# WL_RFFC.net
KiCad netlist of a schematic drawn in Altium Designer
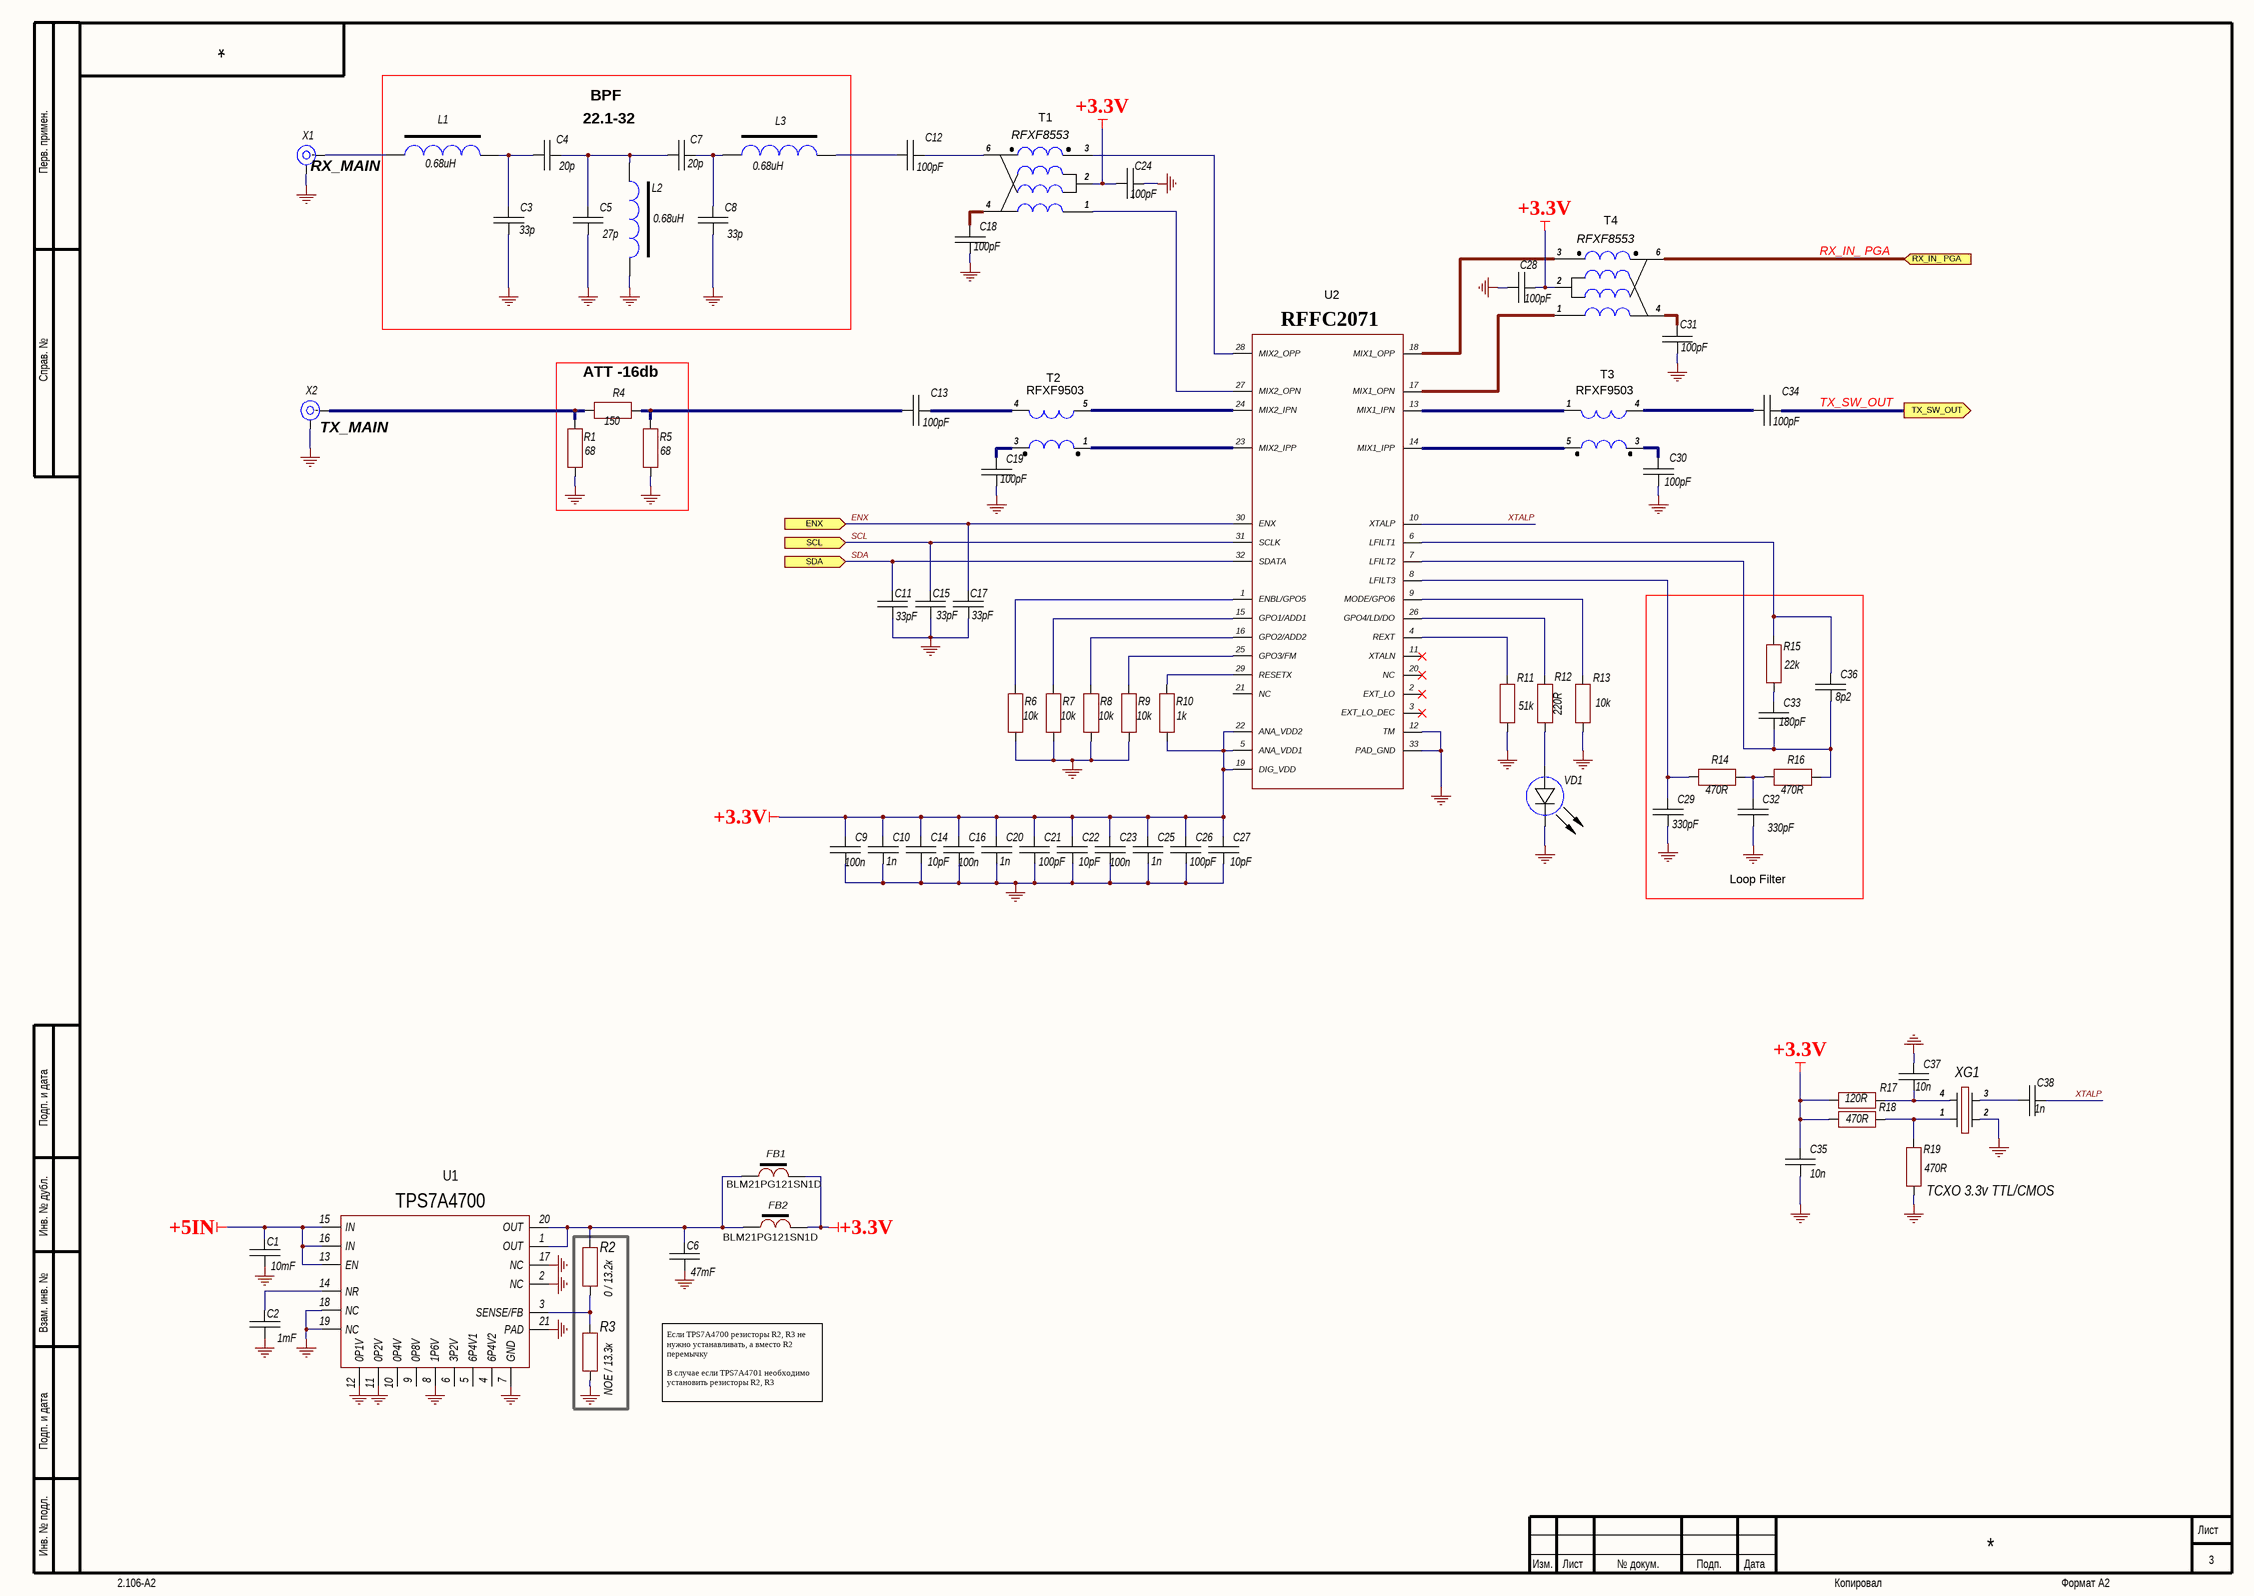
[diagram p0: WL_RFFC.SchDoc]

(export (version "E")
  (design (tool "Eeschema 10.0.6"))
  (components
    (comp (ref "C1")
      (value "10mF")
      (footprint "standard:CH1206C")
      (libsource (lib "Discrete") (part "Capacitor"))
    )
    (comp (ref "C2")
      (value "1mF")
      (footprint "standard:CH0805C")
      (libsource (lib "Discrete") (part "Capacitor"))
    )
    (comp (ref "C3")
      (value "33p")
      (footprint "standard:CH0805C")
      (libsource (lib "Discrete") (part "Capacitor"))
    )
    (comp (ref "C4")
      (value "20p")
      (footprint "standard:CH0805C")
      (libsource (lib "Discrete") (part "Capacitor"))
    )
    (comp (ref "C5")
      (value "27p")
      (footprint "standard:CH0805C")
      (libsource (lib "Discrete") (part "Capacitor"))
    )
    (comp (ref "C6")
      (value "47mF")
      (footprint "standard:CH1206C")
      (libsource (lib "Discrete") (part "Capacitor"))
    )
    (comp (ref "C7")
      (value "20p")
      (footprint "standard:CH0805C")
      (libsource (lib "Discrete") (part "Capacitor"))
    )
    (comp (ref "C8")
      (value "33p")
      (footprint "standard:CH0805C")
      (libsource (lib "Discrete") (part "Capacitor"))
    )
    (comp (ref "C9")
      (value "100n")
      (footprint "standard:CH0805C")
      (libsource (lib "Discrete") (part "Capacitor"))
    )
    (comp (ref "C10")
      (value "1n")
      (footprint "standard:CH0805C")
      (libsource (lib "Discrete") (part "Capacitor"))
    )
    (comp (ref "C11")
      (value "33pF")
      (footprint "standard:CH0805C")
      (libsource (lib "Discrete") (part "Capacitor"))
    )
    (comp (ref "C12")
      (value "100pF")
      (footprint "standard:CH0805C")
      (libsource (lib "Discrete") (part "Capacitor"))
    )
    (comp (ref "C13")
      (value "100pF")
      (footprint "standard:CH0805C")
      (libsource (lib "Discrete") (part "Capacitor"))
    )
    (comp (ref "C14")
      (value "10pF")
      (footprint "standard:CH0805C")
      (libsource (lib "Discrete") (part "Capacitor"))
    )
    (comp (ref "C15")
      (value "33pF")
      (footprint "standard:CH0805C")
      (libsource (lib "Discrete") (part "Capacitor"))
    )
    (comp (ref "C16")
      (value "100n")
      (footprint "standard:CH0805C")
      (libsource (lib "Discrete") (part "Capacitor"))
    )
    (comp (ref "C17")
      (value "33pF")
      (footprint "standard:CH0805C")
      (libsource (lib "Discrete") (part "Capacitor"))
    )
    (comp (ref "C18")
      (value "100pF")
      (footprint "standard:CH0805C")
      (libsource (lib "Discrete") (part "Capacitor"))
    )
    (comp (ref "C19")
      (value "100pF")
      (footprint "standard:CH0805C")
      (libsource (lib "Discrete") (part "Capacitor"))
    )
    (comp (ref "C20")
      (value "1n")
      (footprint "standard:CH0805C")
      (libsource (lib "Discrete") (part "Capacitor"))
    )
    (comp (ref "C21")
      (value "100pF")
      (footprint "standard:CH0805C")
      (libsource (lib "Discrete") (part "Capacitor"))
    )
    (comp (ref "C22")
      (value "10pF")
      (footprint "standard:CH0805C")
      (libsource (lib "Discrete") (part "Capacitor"))
    )
    (comp (ref "C23")
      (value "100n")
      (footprint "standard:CH0805C")
      (libsource (lib "Discrete") (part "Capacitor"))
    )
    (comp (ref "C24")
      (value "100pF")
      (footprint "standard:CH0805C")
      (libsource (lib "Discrete") (part "Capacitor"))
    )
    (comp (ref "C25")
      (value "1n")
      (footprint "standard:CH0805C")
      (libsource (lib "Discrete") (part "Capacitor"))
    )
    (comp (ref "C26")
      (value "100pF")
      (footprint "standard:CH0805C")
      (libsource (lib "Discrete") (part "Capacitor"))
    )
    (comp (ref "C27")
      (value "10pF")
      (footprint "standard:CH0805C")
      (libsource (lib "Discrete") (part "Capacitor"))
    )
    (comp (ref "C28")
      (value "100pF")
      (footprint "standard:CH0805C")
      (libsource (lib "Discrete") (part "Capacitor"))
    )
    (comp (ref "C29")
      (value "330pF")
      (footprint "standard:CH0805C")
      (libsource (lib "Discrete") (part "Capacitor"))
    )
    (comp (ref "C30")
      (value "100pF")
      (footprint "standard:CH0805C")
      (libsource (lib "Discrete") (part "Capacitor"))
    )
    (comp (ref "C31")
      (value "100pF")
      (footprint "standard:CH0805C")
      (libsource (lib "Discrete") (part "Capacitor"))
    )
    (comp (ref "C32")
      (value "330pF")
      (footprint "standard:CH0805C")
      (libsource (lib "Discrete") (part "Capacitor"))
    )
    (comp (ref "C33")
      (value "180pF")
      (footprint "standard:CH0805C")
      (libsource (lib "Discrete") (part "Capacitor"))
    )
    (comp (ref "C34")
      (value "100pF")
      (footprint "standard:CH0805C")
      (libsource (lib "Discrete") (part "Capacitor"))
    )
    (comp (ref "C35")
      (value "10n")
      (footprint "standard:CH0805C")
      (libsource (lib "Discrete") (part "Capacitor"))
    )
    (comp (ref "C36")
      (value "8p2")
      (footprint "standard:CH0805C")
      (libsource (lib "Discrete") (part "Capacitor"))
    )
    (comp (ref "C37")
      (value "10n")
      (footprint "standard:CH0805C")
      (libsource (lib "Discrete") (part "Capacitor"))
    )
    (comp (ref "C38")
      (value "1n")
      (footprint "standard:CH0805C")
      (libsource (lib "Discrete") (part "Capacitor"))
    )
    (comp (ref "FB1")
      (value "BLM21PG121SN1D")
      (footprint "CH0805L")
      (libsource (lib "Discrete") (part "FB-1"))
    )
    (comp (ref "FB2")
      (value "BLM21PG121SN1D")
      (footprint "CH0805L")
      (libsource (lib "Discrete") (part "FB-1"))
    )
    (comp (ref "L1") (value "0.68uH") (footprint "L1210") (libsource (lib "Transformers") (part "TRANS")))
    (comp (ref "L2") (value "0.68uH") (footprint "L1210") (libsource (lib "") (part "TRANS_1")))
    (comp (ref "L3") (value "0.68uH") (footprint "L1210") (libsource (lib "Transformers") (part "TRANS")))
    (comp (ref "R1") (value "68") (footprint "standard:CH1206R") (libsource (lib "") (part "Resistor_1")))
    (comp (ref "R2")
      (value "0 / 13.2к")
      (footprint "standard:CH0805R")
      (libsource (lib "Discrete") (part "Resistor"))
    )
    (comp (ref "R3")
      (value "NOE / 13.3к")
      (footprint "standard:CH0805R")
      (libsource (lib "Discrete") (part "Resistor"))
    )
    (comp (ref "R4") (value "150") (footprint "standard:CH1206R") (libsource (lib "") (part "Resistor_2")))
    (comp (ref "R5") (value "68") (footprint "standard:CH1206R") (libsource (lib "") (part "Resistor_1")))
    (comp (ref "R6") (value "10k") (footprint "standard:CH0805R") (libsource (lib "") (part "Resistor_1")))
    (comp (ref "R7") (value "10k") (footprint "standard:CH0805R") (libsource (lib "") (part "Resistor_1")))
    (comp (ref "R8") (value "10k") (footprint "standard:CH0805R") (libsource (lib "") (part "Resistor_1")))
    (comp (ref "R9") (value "10k") (footprint "standard:CH0805R") (libsource (lib "") (part "Resistor_1")))
    (comp (ref "R10") (value "1k") (footprint "standard:CH0805R") (libsource (lib "") (part "Resistor_1")))
    (comp (ref "R11") (value "51k") (footprint "standard:CH0805R") (libsource (lib "") (part "Resistor_1")))
    (comp (ref "R12") (value "220R") (footprint "standard:CH0805R") (libsource (lib "") (part "Resistor_1")))
    (comp (ref "R13") (value "10k") (footprint "standard:CH0805R") (libsource (lib "") (part "Resistor_1")))
    (comp (ref "R14") (value "470R") (footprint "standard:CH0805R") (libsource (lib "") (part "Resistor_2")))
    (comp (ref "R15")
      (value "22k")
      (footprint "standard:CH0805R")
      (libsource (lib "Discrete") (part "Resistor"))
    )
    (comp (ref "R16") (value "470R") (footprint "standard:CH0805R") (libsource (lib "") (part "Resistor_2")))
    (comp (ref "R17") (value "120R") (footprint "standard:CH0805R") (libsource (lib "") (part "Resistor_2")))
    (comp (ref "R18") (value "470R") (footprint "standard:CH0805R") (libsource (lib "") (part "Resistor_2")))
    (comp (ref "R19")
      (value "470R")
      (footprint "standard:CH0805R")
      (libsource (lib "Discrete") (part "Resistor"))
    )
    (comp (ref "T1")
      (value "RFXF8553")
      (footprint "TC4-1-ADT4-6")
      (libsource (lib "Transformers") (part "RFXF8553"))
    )
    (comp (ref "T2")
      (value "RFXF9503")
      (footprint "TC4-1/RFXF8553")
      (libsource (lib "Transformers") (part "RFXF9503"))
    )
    (comp (ref "T3") (value "RFXF9503") (footprint "TC4-1/RFXF8553") (libsource (lib "") (part "RFXF9503_1")))
    (comp (ref "T4") (value "RFXF8553") (footprint "TC4-1-ADT4-6") (libsource (lib "") (part "RFXF8553_1")))
    (comp (ref "U1")
      (value "TPS7A4700")
      (footprint "20-VQFN (5x5 mm)")
      (libsource (lib "Power Supplies") (part "TPS7A4700"))
    )
    (comp (ref "U2")
      (value "RFFC2071")
      (footprint "32-VQFN (5x5 mm)")
      (libsource (lib "Digital") (part "RFFC2071"))
    )
    (comp (ref "VD1") (value "*") (footprint "standard:CH0805LB") (libsource (lib "Discrete") (part "LED")))
    (comp (ref "X1")
      (value "RX_MAIN")
      (footprint "custom:CON: SMA")
      (description "RF")
      (libsource (lib "Connectors") (part "SMA"))
    )
    (comp (ref "X2")
      (value "TX_MAIN")
      (footprint "custom:CON: SMA")
      (description "RF")
      (libsource (lib "Connectors") (part "SMA"))
    )
    (comp (ref "XG1")
      (value "TCXO 3.3v TTL/CMOS")
      (footprint "TCXO")
      (libsource (lib "Discrete") (part "Generator"))
    )
  )
  (nets
    (net (code "1") (name "+3.3V") (class "Default")
      (node (ref "C10") (pin "2") (pinfunction "2_2") (pintype "power_in"))
      (node (ref "C14") (pin "2") (pinfunction "2_2") (pintype "power_in"))
      (node (ref "C16") (pin "2") (pinfunction "2_2") (pintype "power_in"))
      (node (ref "C20") (pin "2") (pinfunction "2_2") (pintype "power_in"))
      (node (ref "C21") (pin "2") (pinfunction "2_2") (pintype "power_in"))
      (node (ref "C22") (pin "2") (pinfunction "2_2") (pintype "power_in"))
      (node (ref "C23") (pin "2") (pinfunction "2_2") (pintype "power_in"))
      (node (ref "C24") (pin "2") (pinfunction "2_2") (pintype "power_in"))
      (node (ref "C25") (pin "2") (pinfunction "2_2") (pintype "power_in"))
      (node (ref "C26") (pin "2") (pinfunction "2_2") (pintype "power_in"))
      (node (ref "C27") (pin "2") (pinfunction "2_2") (pintype "power_in"))
      (node (ref "C28") (pin "2") (pinfunction "2_2") (pintype "power_in"))
      (node (ref "C35") (pin "2") (pinfunction "2_2") (pintype "power_in"))
      (node (ref "C9") (pin "2") (pinfunction "2_2") (pintype "power_in"))
      (node (ref "FB1") (pin "2") (pinfunction "2_2") (pintype "passive"))
      (node (ref "FB2") (pin "2") (pinfunction "2_2") (pintype "passive"))
      (node (ref "R10") (pin "2") (pinfunction "2_2") (pintype "passive"))
      (node (ref "R17") (pin "1") (pinfunction "1_1") (pintype "passive"))
      (node (ref "R18") (pin "1") (pinfunction "1_1") (pintype "passive"))
      (node (ref "T1") (pin "2") (pinfunction "2_2") (pintype "passive"))
      (node (ref "T4") (pin "2") (pinfunction "2_2") (pintype "passive"))
      (node (ref "U2") (pin "19") (pinfunction "DIG_VDD_19") (pintype "passive"))
      (node (ref "U2") (pin "22") (pinfunction "ANA_VDD2_22") (pintype "passive"))
      (node (ref "U2") (pin "5") (pinfunction "ANA_VDD1_5") (pintype "passive"))
    )
    (net (code "2") (name "+5IN") (class "Default")
      (node (ref "C1") (pin "2") (pinfunction "2_2") (pintype "power_in"))
      (node (ref "U1") (pin "13") (pinfunction "EN_13") (pintype "power_in"))
      (node (ref "U1") (pin "15") (pinfunction "IN_15") (pintype "power_in"))
      (node (ref "U1") (pin "16") (pinfunction "IN_16") (pintype "power_in"))
    )
    (net (code "3") (name "/ENX") (class "Default")
      (node (ref "C17") (pin "2") (pinfunction "2_2") (pintype "power_in"))
      (node (ref "U2") (pin "30") (pinfunction "ENX_30") (pintype "passive"))
    )
    (net (code "4") (name "/RX_IN_ PGA") (class "Default")
      (node (ref "T4") (pin "6") (pinfunction "6_6") (pintype "passive"))
    )
    (net (code "5") (name "/SCL") (class "Default")
      (node (ref "C15") (pin "2") (pinfunction "2_2") (pintype "power_in"))
      (node (ref "U2") (pin "31") (pinfunction "SCLK_31") (pintype "passive"))
    )
    (net (code "6") (name "/SDA") (class "Default")
      (node (ref "C11") (pin "2") (pinfunction "2_2") (pintype "power_in"))
      (node (ref "U2") (pin "32") (pinfunction "SDATA_32") (pintype "passive"))
    )
    (net (code "7") (name "/TX_SW_OUT") (class "Default")
      (node (ref "C34") (pin "1") (pinfunction "1_1") (pintype "power_in"))
    )
    (net (code "8") (name "/XTALP") (class "Default")
      (node (ref "C38") (pin "1") (pinfunction "1_1") (pintype "power_in"))
      (node (ref "U2") (pin "10") (pinfunction "XTALP_10") (pintype "passive"))
    )
    (net (code "9") (name "GND") (class "Default")
      (node (ref "C1") (pin "1") (pinfunction "1_1") (pintype "power_in"))
      (node (ref "C10") (pin "1") (pinfunction "1_1") (pintype "power_in"))
      (node (ref "C11") (pin "1") (pinfunction "1_1") (pintype "power_in"))
      (node (ref "C14") (pin "1") (pinfunction "1_1") (pintype "power_in"))
      (node (ref "C15") (pin "1") (pinfunction "1_1") (pintype "power_in"))
      (node (ref "C16") (pin "1") (pinfunction "1_1") (pintype "power_in"))
      (node (ref "C17") (pin "1") (pinfunction "1_1") (pintype "power_in"))
      (node (ref "C18") (pin "2") (pinfunction "2_2") (pintype "power_in"))
      (node (ref "C19") (pin "2") (pinfunction "2_2") (pintype "power_in"))
      (node (ref "C2") (pin "1") (pinfunction "1_1") (pintype "power_in"))
      (node (ref "C20") (pin "1") (pinfunction "1_1") (pintype "power_in"))
      (node (ref "C21") (pin "1") (pinfunction "1_1") (pintype "power_in"))
      (node (ref "C22") (pin "1") (pinfunction "1_1") (pintype "power_in"))
      (node (ref "C23") (pin "1") (pinfunction "1_1") (pintype "power_in"))
      (node (ref "C24") (pin "1") (pinfunction "1_1") (pintype "power_in"))
      (node (ref "C25") (pin "1") (pinfunction "1_1") (pintype "power_in"))
      (node (ref "C26") (pin "1") (pinfunction "1_1") (pintype "power_in"))
      (node (ref "C27") (pin "1") (pinfunction "1_1") (pintype "power_in"))
      (node (ref "C28") (pin "1") (pinfunction "1_1") (pintype "power_in"))
      (node (ref "C29") (pin "1") (pinfunction "1_1") (pintype "power_in"))
      (node (ref "C3") (pin "1") (pinfunction "1_1") (pintype "power_in"))
      (node (ref "C30") (pin "2") (pinfunction "2_2") (pintype "power_in"))
      (node (ref "C31") (pin "2") (pinfunction "2_2") (pintype "power_in"))
      (node (ref "C32") (pin "1") (pinfunction "1_1") (pintype "power_in"))
      (node (ref "C35") (pin "1") (pinfunction "1_1") (pintype "power_in"))
      (node (ref "C37") (pin "2") (pinfunction "2_2") (pintype "power_in"))
      (node (ref "C5") (pin "1") (pinfunction "1_1") (pintype "power_in"))
      (node (ref "C6") (pin "1") (pinfunction "1_1") (pintype "power_in"))
      (node (ref "C8") (pin "1") (pinfunction "1_1") (pintype "power_in"))
      (node (ref "C9") (pin "1") (pinfunction "1_1") (pintype "power_in"))
      (node (ref "L2") (pin "1") (pinfunction "1_1") (pintype "power_in"))
      (node (ref "R1") (pin "2") (pinfunction "2_2") (pintype "passive"))
      (node (ref "R11") (pin "2") (pinfunction "2_2") (pintype "passive"))
      (node (ref "R13") (pin "2") (pinfunction "2_2") (pintype "passive"))
      (node (ref "R19") (pin "1") (pinfunction "1_1") (pintype "passive"))
      (node (ref "R3") (pin "1") (pinfunction "1_1") (pintype "passive"))
      (node (ref "R5") (pin "2") (pinfunction "2_2") (pintype "passive"))
      (node (ref "R6") (pin "2") (pinfunction "2_2") (pintype "passive"))
      (node (ref "R7") (pin "2") (pinfunction "2_2") (pintype "passive"))
      (node (ref "R8") (pin "2") (pinfunction "2_2") (pintype "passive"))
      (node (ref "R9") (pin "2") (pinfunction "2_2") (pintype "passive"))
      (node (ref "U1") (pin "11") (pinfunction "0P2V_11") (pintype "power_in"))
      (node (ref "U1") (pin "12") (pinfunction "0P1V_12") (pintype "power_in"))
      (node (ref "U1") (pin "17") (pinfunction "NC_17") (pintype "power_in"))
      (node (ref "U1") (pin "18") (pinfunction "NC_18") (pintype "power_in"))
      (node (ref "U1") (pin "19") (pinfunction "NC_19") (pintype "power_in"))
      (node (ref "U1") (pin "2") (pinfunction "NC_2") (pintype "power_in"))
      (node (ref "U1") (pin "21") (pinfunction "PAD_21") (pintype "power_in"))
      (node (ref "U1") (pin "7") (pinfunction "GND_7") (pintype "power_in"))
      (node (ref "U1") (pin "8") (pinfunction "1P6V_8") (pintype "power_in"))
      (node (ref "U2") (pin "12") (pinfunction "TM_12") (pintype "passive"))
      (node (ref "U2") (pin "33") (pinfunction "PAD_GND_33") (pintype "passive"))
      (node (ref "VD1") (pin "2") (pinfunction "C_2") (pintype "passive"))
      (node (ref "X1") (pin "2") (pinfunction "IN_2") (pintype "passive"))
      (node (ref "X2") (pin "2") (pinfunction "IN_2") (pintype "passive"))
      (node (ref "XG1") (pin "2") (pinfunction "2_2") (pintype "passive"))
    )
    (net (code "10") (name "Net-(C3-Pad2)") (class "Default")
      (node (ref "C3") (pin "2") (pinfunction "2_2") (pintype "power_in"))
      (node (ref "C4") (pin "1") (pinfunction "1_1") (pintype "power_in"))
      (node (ref "L1") (pin "2") (pinfunction "2_2") (pintype "power_in"))
    )
    (net (code "11") (name "Net-(C4-Pad2)") (class "Default")
      (node (ref "C4") (pin "2") (pinfunction "2_2") (pintype "power_in"))
      (node (ref "C5") (pin "2") (pinfunction "2_2") (pintype "power_in"))
      (node (ref "C7") (pin "1") (pinfunction "1_1") (pintype "power_in"))
      (node (ref "L2") (pin "2") (pinfunction "2_2") (pintype "power_in"))
    )
    (net (code "12") (name "Net-(C6-Pad2)") (class "Default")
      (node (ref "C6") (pin "2") (pinfunction "2_2") (pintype "power_in"))
      (node (ref "FB1") (pin "1") (pinfunction "1_1") (pintype "passive"))
      (node (ref "FB2") (pin "1") (pinfunction "1_1") (pintype "passive"))
      (node (ref "R2") (pin "2") (pinfunction "2_2") (pintype "passive"))
      (node (ref "U1") (pin "1") (pinfunction "OUT_1") (pintype "power_in"))
      (node (ref "U1") (pin "20") (pinfunction "OUT_20") (pintype "power_in"))
    )
    (net (code "13") (name "Net-(C7-Pad2)") (class "Default")
      (node (ref "C7") (pin "2") (pinfunction "2_2") (pintype "power_in"))
      (node (ref "C8") (pin "2") (pinfunction "2_2") (pintype "power_in"))
      (node (ref "L3") (pin "1") (pinfunction "1_1") (pintype "power_in"))
    )
    (net (code "14") (name "Net-(C12-Pad1)") (class "Default")
      (node (ref "C12") (pin "1") (pinfunction "1_1") (pintype "power_in"))
      (node (ref "L3") (pin "2") (pinfunction "2_2") (pintype "power_in"))
    )
    (net (code "15") (name "Net-(C12-Pad2)") (class "Default")
      (node (ref "C12") (pin "2") (pinfunction "2_2") (pintype "power_in"))
      (node (ref "T1") (pin "6") (pinfunction "6_6") (pintype "passive"))
    )
    (net (code "16") (name "Net-(C13-Pad1)") (class "Default")
      (node (ref "C13") (pin "1") (pinfunction "1_1") (pintype "power_in"))
      (node (ref "R4") (pin "2") (pinfunction "2_2") (pintype "passive"))
      (node (ref "R5") (pin "1") (pinfunction "1_1") (pintype "passive"))
    )
    (net (code "17") (name "Net-(C13-Pad2)") (class "Default")
      (node (ref "C13") (pin "2") (pinfunction "2_2") (pintype "power_in"))
      (node (ref "T2") (pin "4") (pinfunction "4_4") (pintype "passive"))
    )
    (net (code "18") (name "Net-(C18-Pad1)") (class "Default")
      (node (ref "C18") (pin "1") (pinfunction "1_1") (pintype "power_in"))
      (node (ref "T1") (pin "4") (pinfunction "4_4") (pintype "passive"))
    )
    (net (code "19") (name "Net-(C19-Pad1)") (class "Default")
      (node (ref "C19") (pin "1") (pinfunction "1_1") (pintype "power_in"))
      (node (ref "T2") (pin "3") (pinfunction "3_3") (pintype "passive"))
    )
    (net (code "20") (name "Net-(C30-Pad1)") (class "Default")
      (node (ref "C30") (pin "1") (pinfunction "1_1") (pintype "power_in"))
      (node (ref "T3") (pin "3") (pinfunction "3_3") (pintype "passive"))
    )
    (net (code "21") (name "Net-(C31-Pad1)") (class "Default")
      (node (ref "C31") (pin "1") (pinfunction "1_1") (pintype "power_in"))
      (node (ref "T4") (pin "4") (pinfunction "4_4") (pintype "passive"))
    )
    (net (code "22") (name "Net-(C32-Pad2)") (class "Default")
      (node (ref "C32") (pin "2") (pinfunction "2_2") (pintype "power_in"))
      (node (ref "R14") (pin "2") (pinfunction "2_2") (pintype "passive"))
      (node (ref "R16") (pin "1") (pinfunction "1_1") (pintype "passive"))
    )
    (net (code "23") (name "Net-(C33-Pad2)") (class "Default")
      (node (ref "C33") (pin "2") (pinfunction "2_2") (pintype "power_in"))
      (node (ref "R15") (pin "1") (pinfunction "1_1") (pintype "passive"))
    )
    (net (code "24") (name "Net-(C34-Pad2)") (class "Default")
      (node (ref "C34") (pin "2") (pinfunction "2_2") (pintype "power_in"))
      (node (ref "T3") (pin "4") (pinfunction "4_4") (pintype "passive"))
    )
    (net (code "25") (name "Net-(C37-Pad1)") (class "Default")
      (node (ref "C37") (pin "1") (pinfunction "1_1") (pintype "power_in"))
      (node (ref "R17") (pin "2") (pinfunction "2_2") (pintype "passive"))
      (node (ref "XG1") (pin "4") (pinfunction "4_4") (pintype "passive"))
    )
    (net (code "26") (name "Net-(C38-Pad2)") (class "Default")
      (node (ref "C38") (pin "2") (pinfunction "2_2") (pintype "power_in"))
      (node (ref "XG1") (pin "3") (pinfunction "3_3") (pintype "passive"))
    )
    (net (code "27") (name "Net-(L1-Pad1)") (class "Default")
      (node (ref "L1") (pin "1") (pinfunction "1_1") (pintype "power_in"))
      (node (ref "X1") (pin "1") (pinfunction "IN_1") (pintype "passive"))
    )
    (net (code "28") (name "Net-(R1-Pad1)") (class "Default")
      (node (ref "R1") (pin "1") (pinfunction "1_1") (pintype "passive"))
      (node (ref "R4") (pin "1") (pinfunction "1_1") (pintype "passive"))
      (node (ref "X2") (pin "1") (pinfunction "IN_1") (pintype "passive"))
    )
    (net (code "29") (name "Net-(R18-Pad2)") (class "Default")
      (node (ref "R18") (pin "2") (pinfunction "2_2") (pintype "passive"))
      (node (ref "R19") (pin "2") (pinfunction "2_2") (pintype "passive"))
      (node (ref "XG1") (pin "1") (pinfunction "1_1") (pintype "passive"))
    )
    (net (code "30") (name "Net-(U1-NR)") (class "Default")
      (node (ref "C2") (pin "2") (pinfunction "2_2") (pintype "power_in"))
      (node (ref "U1") (pin "14") (pinfunction "NR_14") (pintype "power_in"))
    )
    (net (code "31") (name "Net-(U1-SENSE{slash}FB)") (class "Default")
      (node (ref "R2") (pin "1") (pinfunction "1_1") (pintype "passive"))
      (node (ref "R3") (pin "2") (pinfunction "2_2") (pintype "passive"))
      (node (ref "U1") (pin "3") (pinfunction "SENSE/FB_3") (pintype "power_in"))
    )
    (net (code "32") (name "Net-(U2-ENBL{slash}GPO5)") (class "Default")
      (node (ref "R6") (pin "1") (pinfunction "1_1") (pintype "passive"))
      (node (ref "U2") (pin "1") (pinfunction "ENBL/GPO5_1") (pintype "passive"))
    )
    (net (code "33") (name "Net-(U2-GPO1{slash}ADD1)") (class "Default")
      (node (ref "R7") (pin "1") (pinfunction "1_1") (pintype "passive"))
      (node (ref "U2") (pin "15") (pinfunction "GPO1/ADD1_15") (pintype "passive"))
    )
    (net (code "34") (name "Net-(U2-GPO2{slash}ADD2)") (class "Default")
      (node (ref "R8") (pin "1") (pinfunction "1_1") (pintype "passive"))
      (node (ref "U2") (pin "16") (pinfunction "GPO2/ADD2_16") (pintype "passive"))
    )
    (net (code "35") (name "Net-(U2-GPO3{slash}FM)") (class "Default")
      (node (ref "R9") (pin "1") (pinfunction "1_1") (pintype "passive"))
      (node (ref "U2") (pin "25") (pinfunction "GPO3/FM_25") (pintype "passive"))
    )
    (net (code "36") (name "Net-(U2-GPO4{slash}LD{slash}DO)") (class "Default")
      (node (ref "R12") (pin "1") (pinfunction "1_1") (pintype "passive"))
      (node (ref "U2") (pin "26") (pinfunction "GPO4/LD/DO_26") (pintype "passive"))
    )
    (net (code "37") (name "Net-(U2-LFILT1)") (class "Default")
      (node (ref "C36") (pin "2") (pinfunction "2_2") (pintype "power_in"))
      (node (ref "R15") (pin "2") (pinfunction "2_2") (pintype "passive"))
      (node (ref "U2") (pin "6") (pinfunction "LFILT1_6") (pintype "passive"))
    )
    (net (code "38") (name "Net-(U2-LFILT2)") (class "Default")
      (node (ref "C33") (pin "1") (pinfunction "1_1") (pintype "power_in"))
      (node (ref "C36") (pin "1") (pinfunction "1_1") (pintype "power_in"))
      (node (ref "R16") (pin "2") (pinfunction "2_2") (pintype "passive"))
      (node (ref "U2") (pin "7") (pinfunction "LFILT2_7") (pintype "passive"))
    )
    (net (code "39") (name "Net-(U2-LFILT3)") (class "Default")
      (node (ref "C29") (pin "2") (pinfunction "2_2") (pintype "power_in"))
      (node (ref "R14") (pin "1") (pinfunction "1_1") (pintype "passive"))
      (node (ref "U2") (pin "8") (pinfunction "LFILT3_8") (pintype "passive"))
    )
    (net (code "40") (name "Net-(U2-MIX1_IPN)") (class "Default")
      (node (ref "T3") (pin "1") (pinfunction "1_1") (pintype "passive"))
      (node (ref "U2") (pin "13") (pinfunction "MIX1_IPN_13") (pintype "passive"))
    )
    (net (code "41") (name "Net-(U2-MIX1_IPP)") (class "Default")
      (node (ref "T3") (pin "5") (pinfunction "5_5") (pintype "passive"))
      (node (ref "U2") (pin "14") (pinfunction "MIX1_IPP_14") (pintype "passive"))
    )
    (net (code "42") (name "Net-(U2-MIX1_OPN)") (class "Default")
      (node (ref "T4") (pin "1") (pinfunction "1_1") (pintype "passive"))
      (node (ref "U2") (pin "17") (pinfunction "MIX1_OPN_17") (pintype "passive"))
    )
    (net (code "43") (name "Net-(U2-MIX1_OPP)") (class "Default")
      (node (ref "T4") (pin "3") (pinfunction "3_3") (pintype "passive"))
      (node (ref "U2") (pin "18") (pinfunction "MIX1_OPP_18") (pintype "passive"))
    )
    (net (code "44") (name "Net-(U2-MIX2_IPN)") (class "Default")
      (node (ref "T2") (pin "5") (pinfunction "5_5") (pintype "passive"))
      (node (ref "U2") (pin "24") (pinfunction "MIX2_IPN_24") (pintype "passive"))
    )
    (net (code "45") (name "Net-(U2-MIX2_IPP)") (class "Default")
      (node (ref "T2") (pin "1") (pinfunction "1_1") (pintype "passive"))
      (node (ref "U2") (pin "23") (pinfunction "MIX2_IPP_23") (pintype "passive"))
    )
    (net (code "46") (name "Net-(U2-MIX2_OPN)") (class "Default")
      (node (ref "T1") (pin "1") (pinfunction "1_1") (pintype "passive"))
      (node (ref "U2") (pin "27") (pinfunction "MIX2_OPN_27") (pintype "passive"))
    )
    (net (code "47") (name "Net-(U2-MIX2_OPP)") (class "Default")
      (node (ref "T1") (pin "3") (pinfunction "3_3") (pintype "passive"))
      (node (ref "U2") (pin "28") (pinfunction "MIX2_OPP_28") (pintype "passive"))
    )
    (net (code "48") (name "Net-(U2-MODE{slash}GPO6)") (class "Default")
      (node (ref "R13") (pin "1") (pinfunction "1_1") (pintype "passive"))
      (node (ref "U2") (pin "9") (pinfunction "MODE/GPO6_9") (pintype "passive"))
    )
    (net (code "49") (name "Net-(U2-RESETX)") (class "Default")
      (node (ref "R10") (pin "1") (pinfunction "1_1") (pintype "passive"))
      (node (ref "U2") (pin "29") (pinfunction "RESETX_29") (pintype "passive"))
    )
    (net (code "50") (name "Net-(U2-REXT)") (class "Default")
      (node (ref "R11") (pin "1") (pinfunction "1_1") (pintype "passive"))
      (node (ref "U2") (pin "4") (pinfunction "REXT_4") (pintype "passive"))
    )
    (net (code "51") (name "Net-(VD1-A)") (class "Default")
      (node (ref "R12") (pin "2") (pinfunction "2_2") (pintype "passive"))
      (node (ref "VD1") (pin "1") (pinfunction "A_1") (pintype "passive"))
    )
    (net (code "52") (name "unconnected-(U1-0P4V-Pad10)") (class "Default")
      (node (ref "U1") (pin "10") (pinfunction "0P4V_10") (pintype "power_in"))
    )
    (net (code "53") (name "unconnected-(U1-0P8V-Pad9)") (class "Default")
      (node (ref "U1") (pin "9") (pinfunction "0P8V_9") (pintype "power_in"))
    )
    (net (code "54") (name "unconnected-(U1-3P2V-Pad6)") (class "Default")
      (node (ref "U1") (pin "6") (pinfunction "3P2V_6") (pintype "power_in"))
    )
    (net (code "55") (name "unconnected-(U1-6P4V1-Pad5)") (class "Default")
      (node (ref "U1") (pin "5") (pinfunction "6P4V1_5") (pintype "power_in"))
    )
    (net (code "56") (name "unconnected-(U1-6P4V2-Pad4)") (class "Default")
      (node (ref "U1") (pin "4") (pinfunction "6P4V2_4") (pintype "power_in"))
    )
    (net (code "57") (name "unconnected-(U2-EXT_LO-Pad2)") (class "Default")
      (node (ref "U2") (pin "2") (pinfunction "EXT_LO_2") (pintype "passive+no_connect"))
    )
    (net (code "58") (name "unconnected-(U2-EXT_LO_DEC-Pad3)") (class "Default")
      (node (ref "U2") (pin "3") (pinfunction "EXT_LO_DEC_3") (pintype "passive+no_connect"))
    )
    (net (code "59") (name "unconnected-(U2-NC-Pad20)") (class "Default")
      (node (ref "U2") (pin "20") (pinfunction "NC_20") (pintype "passive+no_connect"))
    )
    (net (code "60") (name "unconnected-(U2-NC-Pad21)") (class "Default")
      (node (ref "U2") (pin "21") (pinfunction "NC_21") (pintype "passive"))
    )
    (net (code "61") (name "unconnected-(U2-XTALN-Pad11)") (class "Default")
      (node (ref "U2") (pin "11") (pinfunction "XTALN_11") (pintype "passive+no_connect"))
    )
  )
)
